# 1uprava4.net
KiCad netlist of a schematic drawn in EAGLE
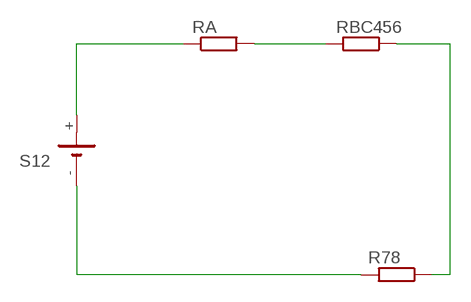
[diagram p0: schematic, sheet 1]

(export (version "E")
  (design (tool "Eeschema 10.0.6"))
  (components
    (comp (ref "R78")
      (value "355R")
      (footprint "eagle-import:0204_7")
      (libsource (lib "eagle-import") (part "R-EU_0204/7"))
    )
    (comp (ref "RA")
      (value "680R")
      (footprint "eagle-import:0204_7")
      (libsource (lib "eagle-import") (part "R-EU_0204/7"))
    )
    (comp (ref "RBC456")
      (value "260R")
      (footprint "eagle-import:0204_7")
      (libsource (lib "eagle-import") (part "R-EU_0204/7"))
    )
    (comp (ref "S12")
      (value "135V")
      (footprint "eagle-import:CH291-1220LF")
      (libsource (lib "eagle-import") (part "CH291-1220LF"))
    )
  )
  (nets
    (net (code "1") (name "Net-(R78-Pad1)") (class "Default")
      (node (ref "R78") (pin "1") (pinfunction "1_1") (pintype "passive"))
      (node (ref "RBC456") (pin "1") (pinfunction "1_1") (pintype "passive"))
    )
    (net (code "2") (name "Net-(R78-Pad2)") (class "Default")
      (node (ref "R78") (pin "2") (pinfunction "2_2") (pintype "passive"))
      (node (ref "S12") (pin "-") (pinfunction "-_-") (pintype "passive"))
    )
    (net (code "3") (name "Net-(RA-Pad1)") (class "Default")
      (node (ref "RA") (pin "1") (pinfunction "1_1") (pintype "passive"))
      (node (ref "S12") (pin "+") (pinfunction "+_+") (pintype "passive"))
    )
    (net (code "4") (name "Net-(RA-Pad2)") (class "Default")
      (node (ref "RA") (pin "2") (pinfunction "2_2") (pintype "passive"))
      (node (ref "RBC456") (pin "2") (pinfunction "2_2") (pintype "passive"))
    )
  )
)
